# PCB-BMDShieldCon.net
KiCad netlist of a schematic drawn in EAGLE
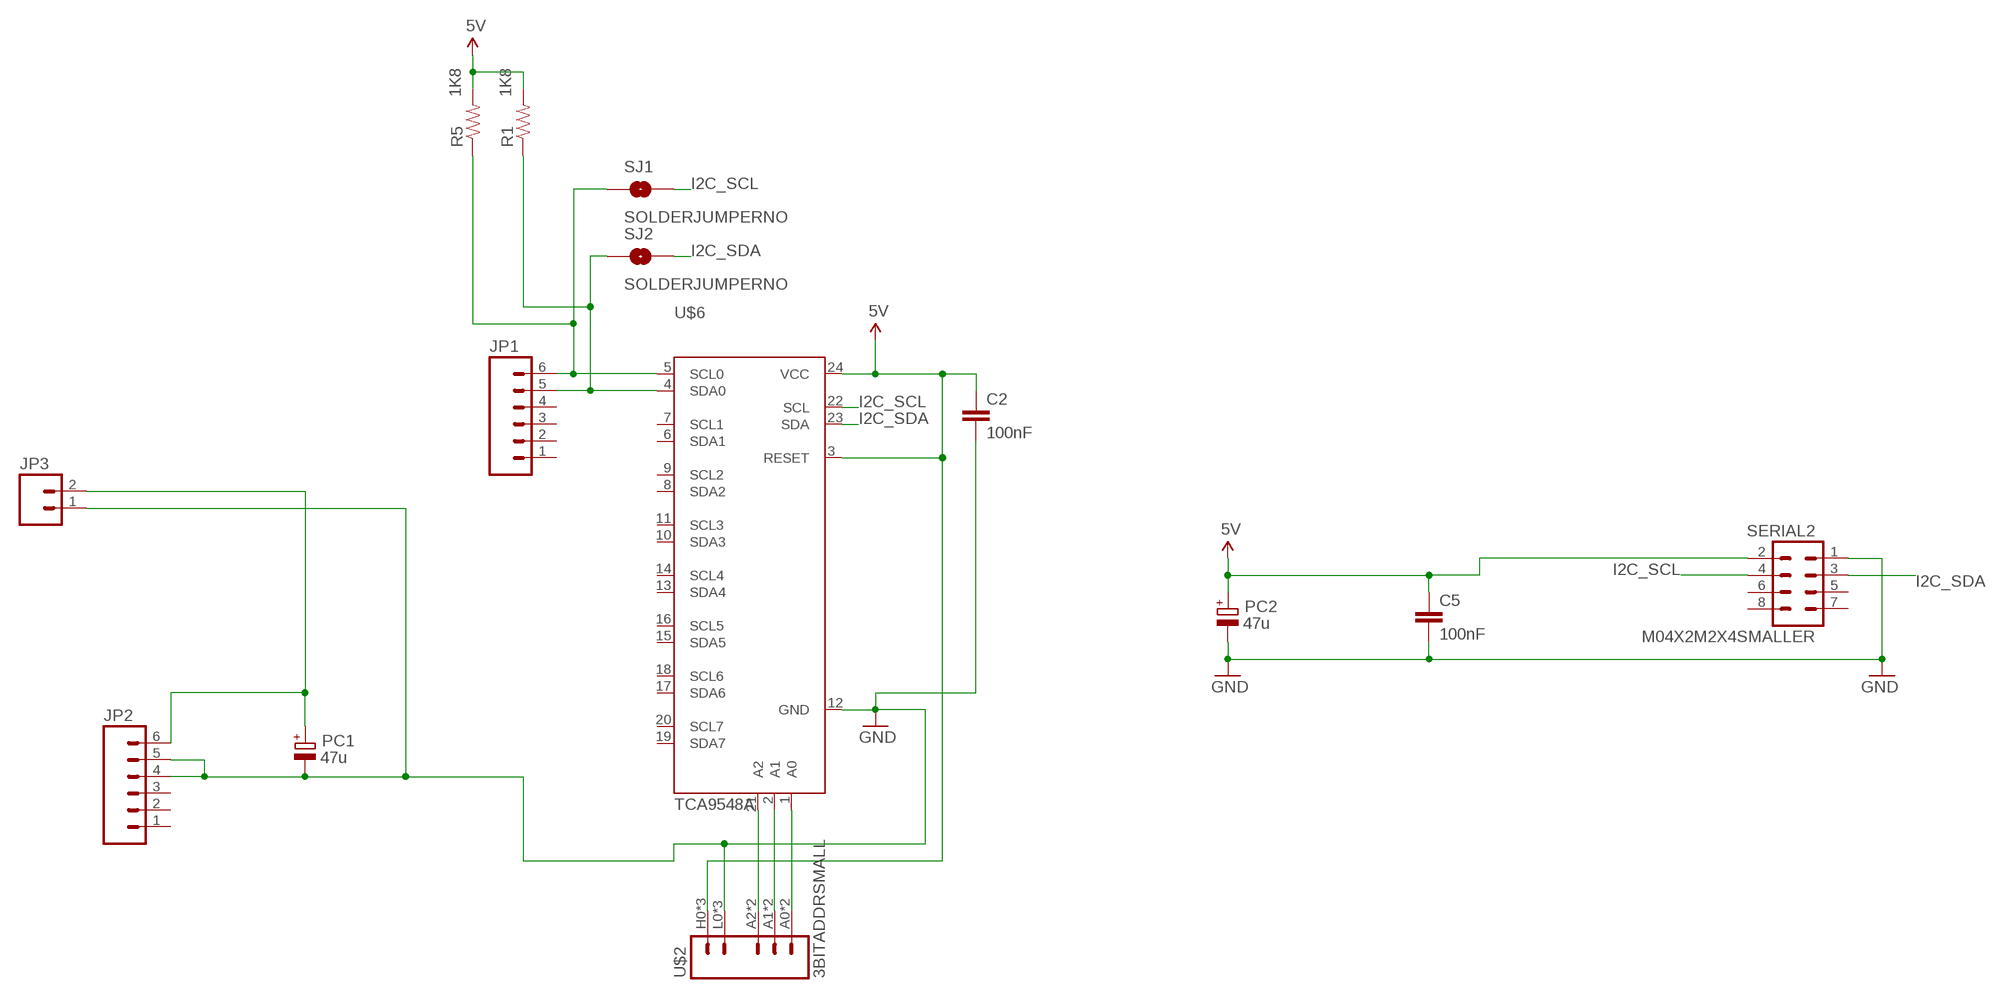
[diagram p0: schematic, sheet 1]

(export (version "E")
  (design (tool "Eeschema 10.0.6"))
  (components
    (comp (ref "C2")
      (value "100nF")
      (footprint "eagle-import:0603-CAP")
      (libsource (lib "eagle-import") (part "CAP0603-CAP"))
    )
    (comp (ref "C5")
      (value "100nF")
      (footprint "eagle-import:0603-CAP")
      (libsource (lib "eagle-import") (part "CAP0603-CAP"))
    )
    (comp (ref "JP1")
      (value "M06SIP")
      (footprint "eagle-import:1X06")
      (libsource (lib "eagle-import") (part "M06SIP"))
    )
    (comp (ref "JP2")
      (value "M06SIP")
      (footprint "eagle-import:1X06")
      (libsource (lib "eagle-import") (part "M06SIP"))
    )
    (comp (ref "JP3")
      (value "M02PTH4")
      (footprint "eagle-import:1X02_XTRA_BIG")
      (libsource (lib "eagle-import") (part "M02PTH4"))
    )
    (comp (ref "PC1")
      (value "47u")
      (footprint "eagle-import:PANASONIC_D")
      (libsource (lib "eagle-import") (part "CPOL-EUD"))
    )
    (comp (ref "PC2")
      (value "47u")
      (footprint "eagle-import:PANASONIC_D")
      (libsource (lib "eagle-import") (part "CPOL-EUD"))
    )
    (comp (ref "R1")
      (value "1K8")
      (footprint "eagle-import:0603-RES")
      (libsource (lib "eagle-import") (part "RESISTOR0603-RES"))
    )
    (comp (ref "R5")
      (value "1K8")
      (footprint "eagle-import:0603-RES")
      (libsource (lib "eagle-import") (part "RESISTOR0603-RES"))
    )
    (comp (ref "SERIAL2")
      (value "M04X2M2X4SMALLER")
      (footprint "eagle-import:M2X4SMALLER")
      (libsource (lib "eagle-import") (part "M04X2M2X4SMALLER"))
    )
    (comp (ref "SJ1")
      (value "SOLDERJUMPERNO")
      (footprint "eagle-import:SJ_2S-NO")
      (libsource (lib "eagle-import") (part "SOLDERJUMPERNO"))
    )
    (comp (ref "SJ2")
      (value "SOLDERJUMPERNO")
      (footprint "eagle-import:SJ_2S-NO")
      (libsource (lib "eagle-import") (part "SOLDERJUMPERNO"))
    )
    (comp (ref "U$2")
      (value "3BITADDRSMALL")
      (footprint "eagle-import:3BITADDR_SMALL")
      (libsource (lib "eagle-import") (part "3BITADDRSMALL"))
    )
    (comp (ref "U$6")
      (value "TCA9548A")
      (footprint "eagle-import:TSSOP24")
      (libsource (lib "eagle-import") (part "TCA9548A"))
    )
  )
  (nets
    (net (code "1") (name "5V") (class "Default")
      (node (ref "C2") (pin "1") (pinfunction "1_1") (pintype "passive"))
      (node (ref "C5") (pin "1") (pinfunction "1_1") (pintype "passive"))
      (node (ref "PC2") (pin "+") (pinfunction "+_+") (pintype "passive"))
      (node (ref "R1") (pin "2") (pinfunction "2_2") (pintype "passive"))
      (node (ref "R5") (pin "2") (pinfunction "2_2") (pintype "passive"))
      (node (ref "SERIAL2") (pin "2") (pinfunction "2_2") (pintype "passive"))
      (node (ref "U$2") (pin "H0") (pinfunction "VCC_H0") (pintype "passive"))
      (node (ref "U$2") (pin "H1") (pinfunction "VCC_H1") (pintype "passive"))
      (node (ref "U$2") (pin "H2") (pinfunction "VCC_H2") (pintype "passive"))
      (node (ref "U$6") (pin "24") (pinfunction "VCC_24") (pintype "power_in"))
      (node (ref "U$6") (pin "3") (pinfunction "RESET_3") (pintype "input"))
    )
    (net (code "2") (name "GND") (class "Default")
      (node (ref "C2") (pin "2") (pinfunction "2_2") (pintype "passive"))
      (node (ref "C5") (pin "2") (pinfunction "2_2") (pintype "passive"))
      (node (ref "JP2") (pin "4") (pinfunction "4_4") (pintype "passive"))
      (node (ref "JP2") (pin "5") (pinfunction "5_5") (pintype "passive"))
      (node (ref "JP3") (pin "1") (pinfunction "1_1") (pintype "passive"))
      (node (ref "PC1") (pin "-") (pinfunction "-_-") (pintype "passive"))
      (node (ref "PC2") (pin "-") (pinfunction "-_-") (pintype "passive"))
      (node (ref "SERIAL2") (pin "1") (pinfunction "1_1") (pintype "passive"))
      (node (ref "U$2") (pin "L0") (pinfunction "GND_L0") (pintype "passive"))
      (node (ref "U$2") (pin "L1") (pinfunction "GND_L1") (pintype "passive"))
      (node (ref "U$2") (pin "L2") (pinfunction "GND_L2") (pintype "passive"))
      (node (ref "U$6") (pin "12") (pinfunction "GND_12") (pintype "power_in"))
    )
    (net (code "3") (name "I2C_SCL") (class "Default")
      (node (ref "SERIAL2") (pin "4") (pinfunction "4_4") (pintype "passive"))
      (node (ref "SJ1") (pin "2") (pinfunction "2_2") (pintype "passive"))
      (node (ref "U$6") (pin "22") (pinfunction "SCL_22") (pintype "bidirectional"))
    )
    (net (code "4") (name "I2C_SDA") (class "Default")
      (node (ref "SERIAL2") (pin "3") (pinfunction "3_3") (pintype "passive"))
      (node (ref "SJ2") (pin "2") (pinfunction "2_2") (pintype "passive"))
      (node (ref "U$6") (pin "23") (pinfunction "SDA_23") (pintype "bidirectional"))
    )
    (net (code "5") (name "Net-(JP2-Pad6)") (class "Default")
      (node (ref "JP2") (pin "6") (pinfunction "6_6") (pintype "passive"))
      (node (ref "JP3") (pin "2") (pinfunction "2_2") (pintype "passive"))
      (node (ref "PC1") (pin "+") (pinfunction "+_+") (pintype "passive"))
    )
    (net (code "6") (name "Net-(U$6-A0)") (class "Default")
      (node (ref "U$2") (pin "A0") (pinfunction "A0_A0") (pintype "passive"))
      (node (ref "U$2") (pin "AS0") (pinfunction "A0_AS0") (pintype "passive"))
      (node (ref "U$6") (pin "1") (pinfunction "A0_1") (pintype "input"))
    )
    (net (code "7") (name "Net-(U$6-A1)") (class "Default")
      (node (ref "U$2") (pin "A1") (pinfunction "A1_A1") (pintype "passive"))
      (node (ref "U$2") (pin "AS1") (pinfunction "A1_AS1") (pintype "passive"))
      (node (ref "U$6") (pin "2") (pinfunction "A1_2") (pintype "input"))
    )
    (net (code "8") (name "Net-(U$6-A2)") (class "Default")
      (node (ref "U$2") (pin "A2") (pinfunction "A2_A2") (pintype "passive"))
      (node (ref "U$2") (pin "AS2") (pinfunction "A2_AS2") (pintype "passive"))
      (node (ref "U$6") (pin "21") (pinfunction "A2_21") (pintype "input"))
    )
    (net (code "9") (name "Net-(U$6-SCL0)") (class "Default")
      (node (ref "JP1") (pin "6") (pinfunction "6_6") (pintype "passive"))
      (node (ref "R5") (pin "1") (pinfunction "1_1") (pintype "passive"))
      (node (ref "SJ1") (pin "1") (pinfunction "1_1") (pintype "passive"))
      (node (ref "U$6") (pin "5") (pinfunction "SCL0_5") (pintype "bidirectional"))
    )
    (net (code "10") (name "Net-(U$6-SDA0)") (class "Default")
      (node (ref "JP1") (pin "5") (pinfunction "5_5") (pintype "passive"))
      (node (ref "R1") (pin "1") (pinfunction "1_1") (pintype "passive"))
      (node (ref "SJ2") (pin "1") (pinfunction "1_1") (pintype "passive"))
      (node (ref "U$6") (pin "4") (pinfunction "SDA0_4") (pintype "bidirectional"))
    )
    (net (code "11") (name "unconnected-(JP1-Pad1)") (class "Default")
      (node (ref "JP1") (pin "1") (pinfunction "1_1") (pintype "passive"))
    )
    (net (code "12") (name "unconnected-(JP1-Pad2)") (class "Default")
      (node (ref "JP1") (pin "2") (pinfunction "2_2") (pintype "passive"))
    )
    (net (code "13") (name "unconnected-(JP1-Pad3)") (class "Default")
      (node (ref "JP1") (pin "3") (pinfunction "3_3") (pintype "passive"))
    )
    (net (code "14") (name "unconnected-(JP1-Pad4)") (class "Default")
      (node (ref "JP1") (pin "4") (pinfunction "4_4") (pintype "passive"))
    )
    (net (code "15") (name "unconnected-(JP2-Pad1)") (class "Default")
      (node (ref "JP2") (pin "1") (pinfunction "1_1") (pintype "passive"))
    )
    (net (code "16") (name "unconnected-(JP2-Pad2)") (class "Default")
      (node (ref "JP2") (pin "2") (pinfunction "2_2") (pintype "passive"))
    )
    (net (code "17") (name "unconnected-(JP2-Pad3)") (class "Default")
      (node (ref "JP2") (pin "3") (pinfunction "3_3") (pintype "passive"))
    )
    (net (code "18") (name "unconnected-(SERIAL2-Pad5)") (class "Default")
      (node (ref "SERIAL2") (pin "5") (pinfunction "5_5") (pintype "passive"))
    )
    (net (code "19") (name "unconnected-(SERIAL2-Pad6)") (class "Default")
      (node (ref "SERIAL2") (pin "6") (pinfunction "6_6") (pintype "passive"))
    )
    (net (code "20") (name "unconnected-(SERIAL2-Pad7)") (class "Default")
      (node (ref "SERIAL2") (pin "7") (pinfunction "7_7") (pintype "passive"))
    )
    (net (code "21") (name "unconnected-(SERIAL2-Pad8)") (class "Default")
      (node (ref "SERIAL2") (pin "8") (pinfunction "8_8") (pintype "passive"))
    )
    (net (code "22") (name "unconnected-(U$6-SCL1-Pad7)") (class "Default")
      (node (ref "U$6") (pin "7") (pinfunction "SCL1_7") (pintype "bidirectional"))
    )
    (net (code "23") (name "unconnected-(U$6-SCL2-Pad9)") (class "Default")
      (node (ref "U$6") (pin "9") (pinfunction "SCL2_9") (pintype "bidirectional"))
    )
    (net (code "24") (name "unconnected-(U$6-SCL3-Pad11)") (class "Default")
      (node (ref "U$6") (pin "11") (pinfunction "SCL3_11") (pintype "bidirectional"))
    )
    (net (code "25") (name "unconnected-(U$6-SCL4-Pad14)") (class "Default")
      (node (ref "U$6") (pin "14") (pinfunction "SCL4_14") (pintype "bidirectional"))
    )
    (net (code "26") (name "unconnected-(U$6-SCL5-Pad16)") (class "Default")
      (node (ref "U$6") (pin "16") (pinfunction "SCL5_16") (pintype "bidirectional"))
    )
    (net (code "27") (name "unconnected-(U$6-SCL6-Pad18)") (class "Default")
      (node (ref "U$6") (pin "18") (pinfunction "SCL6_18") (pintype "bidirectional"))
    )
    (net (code "28") (name "unconnected-(U$6-SCL7-Pad20)") (class "Default")
      (node (ref "U$6") (pin "20") (pinfunction "SCL7_20") (pintype "bidirectional"))
    )
    (net (code "29") (name "unconnected-(U$6-SDA1-Pad6)") (class "Default")
      (node (ref "U$6") (pin "6") (pinfunction "SDA1_6") (pintype "bidirectional"))
    )
    (net (code "30") (name "unconnected-(U$6-SDA2-Pad8)") (class "Default")
      (node (ref "U$6") (pin "8") (pinfunction "SDA2_8") (pintype "bidirectional"))
    )
    (net (code "31") (name "unconnected-(U$6-SDA3-Pad10)") (class "Default")
      (node (ref "U$6") (pin "10") (pinfunction "SDA3_10") (pintype "bidirectional"))
    )
    (net (code "32") (name "unconnected-(U$6-SDA4-Pad13)") (class "Default")
      (node (ref "U$6") (pin "13") (pinfunction "SDA4_13") (pintype "bidirectional"))
    )
    (net (code "33") (name "unconnected-(U$6-SDA5-Pad15)") (class "Default")
      (node (ref "U$6") (pin "15") (pinfunction "SDA5_15") (pintype "bidirectional"))
    )
    (net (code "34") (name "unconnected-(U$6-SDA6-Pad17)") (class "Default")
      (node (ref "U$6") (pin "17") (pinfunction "SDA6_17") (pintype "bidirectional"))
    )
    (net (code "35") (name "unconnected-(U$6-SDA7-Pad19)") (class "Default")
      (node (ref "U$6") (pin "19") (pinfunction "SDA7_19") (pintype "bidirectional"))
    )
  )
)
